# Sheet3.net
KiCad netlist of a schematic drawn in Altium Designer
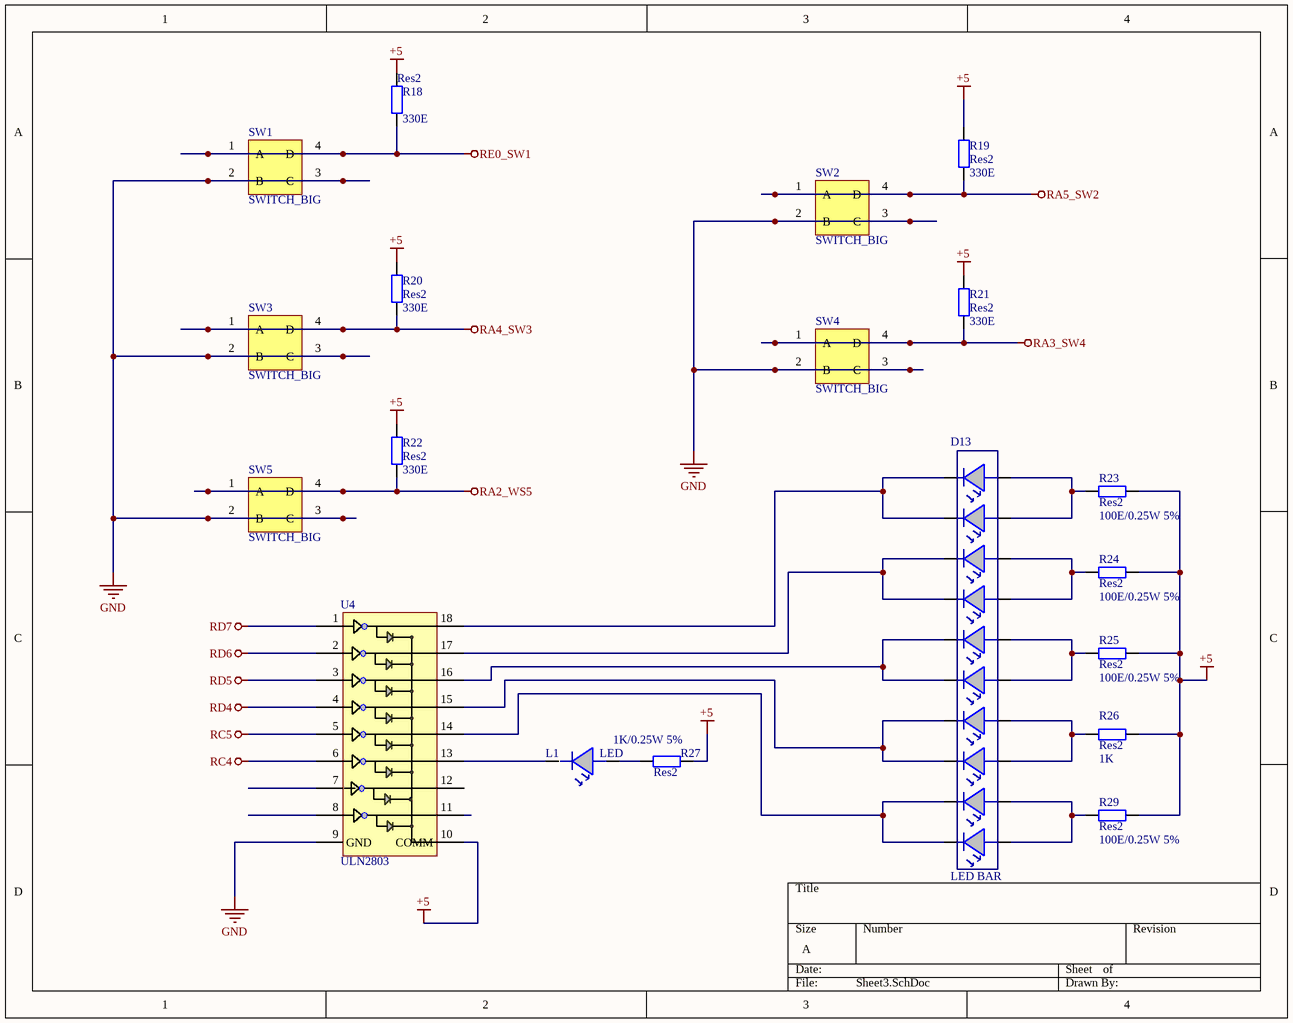
[diagram p0: Sheet3.SchDoc]

(export (version "E")
  (design (tool "Eeschema 10.0.6"))
  (components
    (comp (ref "D13")
      (value "LED BAR")
      (footprint "LED_BAR")
      (libsource (lib "VIJAYIntegrated_Library") (part "LED_BAR"))
    )
    (comp (ref "L1")
      (value "LED")
      (footprint "LED5MM")
      (description "LED_5MM")
      (libsource (lib "Dinesh_New_Integrated_Library") (part "LED_5MM"))
    )
    (comp (ref "R18")
      (value "Res2")
      (footprint "AXIAL-0.4")
      (description "Resistor")
      (fields (field (name "ALTIUM_VALUE") "330E") (field (name "PUBLISHER") "Altium Limited"))
      (libsource (lib "Miscellaneous Devices") (part "Res2"))
    )
    (comp (ref "R19")
      (value "Res2")
      (footprint "AXIAL-0.4")
      (description "Resistor")
      (fields (field (name "ALTIUM_VALUE") "330E") (field (name "PUBLISHER") "Altium Limited"))
      (libsource (lib "Miscellaneous Devices") (part "Res2"))
    )
    (comp (ref "R20")
      (value "Res2")
      (footprint "AXIAL-0.4")
      (description "Resistor")
      (fields (field (name "ALTIUM_VALUE") "330E") (field (name "PUBLISHER") "Altium Limited"))
      (libsource (lib "Miscellaneous Devices") (part "Res2"))
    )
    (comp (ref "R21")
      (value "Res2")
      (footprint "AXIAL-0.4")
      (description "Resistor")
      (fields (field (name "ALTIUM_VALUE") "330E") (field (name "PUBLISHER") "Altium Limited"))
      (libsource (lib "Miscellaneous Devices") (part "Res2"))
    )
    (comp (ref "R22")
      (value "Res2")
      (footprint "AXIAL-0.4")
      (description "Resistor")
      (fields (field (name "ALTIUM_VALUE") "330E") (field (name "PUBLISHER") "Altium Limited"))
      (libsource (lib "Miscellaneous Devices") (part "Res2"))
    )
    (comp (ref "R23")
      (value "Res2")
      (footprint "AXIAL-0.4")
      (description "Resistor")
      (fields (field (name "ALTIUM_VALUE") "100E/0.25W 5%") (field (name "PUBLISHER") "Altium Limited"))
      (libsource (lib "") (part "Res2_1"))
    )
    (comp (ref "R24")
      (value "Res2")
      (footprint "AXIAL-0.4")
      (description "Resistor")
      (fields (field (name "ALTIUM_VALUE") "100E/0.25W 5%") (field (name "PUBLISHER") "Altium Limited"))
      (libsource (lib "") (part "Res2_1"))
    )
    (comp (ref "R25")
      (value "Res2")
      (footprint "AXIAL-0.4")
      (description "Resistor")
      (fields (field (name "ALTIUM_VALUE") "100E/0.25W 5%") (field (name "PUBLISHER") "Altium Limited"))
      (libsource (lib "") (part "Res2_1"))
    )
    (comp (ref "R26")
      (value "Res2")
      (footprint "AXIAL-0.4")
      (description "Resistor")
      (fields (field (name "ALTIUM_VALUE") "1K") (field (name "PUBLISHER") "Altium Limited"))
      (libsource (lib "") (part "Res2_1"))
    )
    (comp (ref "R27")
      (value "Res2")
      (footprint "AXIAL-0.4")
      (description "Resistor")
      (fields (field (name "ALTIUM_VALUE") "1K/0.25W 5%") (field (name "PUBLISHER") "Altium Limited"))
      (libsource (lib "") (part "Res2_2"))
    )
    (comp (ref "R29")
      (value "Res2")
      (footprint "AXIAL-0.4")
      (description "Resistor")
      (fields (field (name "ALTIUM_VALUE") "100E/0.25W 5%") (field (name "PUBLISHER") "Altium Limited"))
      (libsource (lib "") (part "Res2_1"))
    )
    (comp (ref "SW1")
      (value "SWITCH_BIG")
      (footprint "SWITCH - BIG")
      (description "Big size")
      (libsource (lib "Dinesh_New_Integrated_Library") (part "SWITCH_BIG"))
    )
    (comp (ref "SW2")
      (value "SWITCH_BIG")
      (footprint "SWITCH - BIG")
      (description "Big size")
      (libsource (lib "Dinesh_New_Integrated_Library") (part "SWITCH_BIG"))
    )
    (comp (ref "SW3")
      (value "SWITCH_BIG")
      (footprint "SWITCH - BIG")
      (description "Big size")
      (libsource (lib "Dinesh_New_Integrated_Library") (part "SWITCH_BIG"))
    )
    (comp (ref "SW4")
      (value "SWITCH_BIG")
      (footprint "SWITCH - BIG")
      (description "Big size")
      (libsource (lib "Dinesh_New_Integrated_Library") (part "SWITCH_BIG"))
    )
    (comp (ref "SW5")
      (value "SWITCH_BIG")
      (footprint "SWITCH - BIG")
      (description "Big size")
      (libsource (lib "Dinesh_New_Integrated_Library") (part "SWITCH_BIG"))
    )
    (comp (ref "U4")
      (value "ULN2803")
      (footprint "ULN2803")
      (libsource (lib "VIJAYIntegrated_Library") (part "ULN2803"))
    )
  )
  (nets
    (net (code "1") (name "+5") (class "Default")
      (node (ref "R18") (pin "2") (pinfunction "2_2") (pintype "passive"))
      (node (ref "R19") (pin "2") (pinfunction "2_2") (pintype "passive"))
      (node (ref "R20") (pin "2") (pinfunction "2_2") (pintype "passive"))
      (node (ref "R21") (pin "2") (pinfunction "2_2") (pintype "passive"))
      (node (ref "R22") (pin "2") (pinfunction "2_2") (pintype "passive"))
      (node (ref "R23") (pin "2") (pinfunction "2_2") (pintype "passive"))
      (node (ref "R24") (pin "2") (pinfunction "2_2") (pintype "passive"))
      (node (ref "R25") (pin "2") (pinfunction "2_2") (pintype "passive"))
      (node (ref "R26") (pin "2") (pinfunction "2_2") (pintype "passive"))
      (node (ref "R27") (pin "1") (pinfunction "1_1") (pintype "passive"))
      (node (ref "R29") (pin "2") (pinfunction "2_2") (pintype "passive"))
      (node (ref "U4") (pin "10") (pinfunction "COMM_10") (pintype "passive"))
    )
    (net (code "2") (name "GND") (class "Default")
      (node (ref "SW1") (pin "2") (pinfunction "B_2") (pintype "passive"))
      (node (ref "SW1") (pin "3") (pinfunction "C_3") (pintype "passive"))
      (node (ref "SW2") (pin "2") (pinfunction "B_2") (pintype "passive"))
      (node (ref "SW2") (pin "3") (pinfunction "C_3") (pintype "passive"))
      (node (ref "SW3") (pin "2") (pinfunction "B_2") (pintype "passive"))
      (node (ref "SW3") (pin "3") (pinfunction "C_3") (pintype "passive"))
      (node (ref "SW4") (pin "2") (pinfunction "B_2") (pintype "passive"))
      (node (ref "SW4") (pin "3") (pinfunction "C_3") (pintype "passive"))
      (node (ref "SW5") (pin "2") (pinfunction "B_2") (pintype "passive"))
      (node (ref "SW5") (pin "3") (pinfunction "C_3") (pintype "passive"))
      (node (ref "U4") (pin "9") (pinfunction "GND_9") (pintype "passive"))
    )
    (net (code "3") (name "Net-(D13-Pad1)") (class "Default")
      (node (ref "D13") (pin "1") (pinfunction "1_1") (pintype "passive"))
      (node (ref "D13") (pin "2") (pinfunction "2_2") (pintype "passive"))
      (node (ref "R29") (pin "1") (pinfunction "1_1") (pintype "passive"))
    )
    (net (code "4") (name "Net-(D13-Pad3)") (class "Default")
      (node (ref "D13") (pin "3") (pinfunction "3_3") (pintype "passive"))
      (node (ref "D13") (pin "4") (pinfunction "4_4") (pintype "passive"))
      (node (ref "R26") (pin "1") (pinfunction "1_1") (pintype "passive"))
    )
    (net (code "5") (name "Net-(D13-Pad5)") (class "Default")
      (node (ref "D13") (pin "5") (pinfunction "5_5") (pintype "passive"))
      (node (ref "D13") (pin "6") (pinfunction "6_6") (pintype "passive"))
      (node (ref "R25") (pin "1") (pinfunction "1_1") (pintype "passive"))
    )
    (net (code "6") (name "Net-(D13-Pad7)") (class "Default")
      (node (ref "D13") (pin "7") (pinfunction "7_7") (pintype "passive"))
      (node (ref "D13") (pin "8") (pinfunction "8_8") (pintype "passive"))
      (node (ref "R24") (pin "1") (pinfunction "1_1") (pintype "passive"))
    )
    (net (code "7") (name "Net-(D13-Pad10)") (class "Default")
      (node (ref "D13") (pin "10") (pinfunction "10_10") (pintype "passive"))
      (node (ref "D13") (pin "9") (pinfunction "9_9") (pintype "passive"))
      (node (ref "R23") (pin "1") (pinfunction "1_1") (pintype "passive"))
    )
    (net (code "8") (name "Net-(D13-Pad11)") (class "Default")
      (node (ref "D13") (pin "11") (pinfunction "11_11") (pintype "passive"))
      (node (ref "D13") (pin "12") (pinfunction "12_12") (pintype "passive"))
      (node (ref "U4") (pin "18") (pinfunction "18_18") (pintype "passive"))
    )
    (net (code "9") (name "Net-(D13-Pad13)") (class "Default")
      (node (ref "D13") (pin "13") (pinfunction "13_13") (pintype "passive"))
      (node (ref "D13") (pin "14") (pinfunction "14_14") (pintype "passive"))
      (node (ref "U4") (pin "17") (pinfunction "17_17") (pintype "passive"))
    )
    (net (code "10") (name "Net-(D13-Pad15)") (class "Default")
      (node (ref "D13") (pin "15") (pinfunction "15_15") (pintype "passive"))
      (node (ref "D13") (pin "16") (pinfunction "16_16") (pintype "passive"))
      (node (ref "U4") (pin "16") (pinfunction "16_16") (pintype "passive"))
    )
    (net (code "11") (name "Net-(D13-Pad17)") (class "Default")
      (node (ref "D13") (pin "17") (pinfunction "17_17") (pintype "passive"))
      (node (ref "D13") (pin "18") (pinfunction "18_18") (pintype "passive"))
      (node (ref "U4") (pin "15") (pinfunction "15_15") (pintype "passive"))
    )
    (net (code "12") (name "Net-(D13-Pad19)") (class "Default")
      (node (ref "D13") (pin "19") (pinfunction "19_19") (pintype "passive"))
      (node (ref "D13") (pin "20") (pinfunction "20_20") (pintype "passive"))
      (node (ref "U4") (pin "14") (pinfunction "14_14") (pintype "passive"))
    )
    (net (code "13") (name "Net-(L1-A)") (class "Default")
      (node (ref "L1") (pin "1") (pinfunction "A_1") (pintype "passive"))
      (node (ref "R27") (pin "2") (pinfunction "2_2") (pintype "passive"))
    )
    (net (code "14") (name "Net-(L1-B)") (class "Default")
      (node (ref "L1") (pin "2") (pinfunction "B_2") (pintype "passive"))
      (node (ref "U4") (pin "13") (pinfunction "13_13") (pintype "passive"))
    )
    (net (code "15") (name "RA2_WS5") (class "Default")
      (node (ref "R22") (pin "1") (pinfunction "1_1") (pintype "passive"))
      (node (ref "SW5") (pin "1") (pinfunction "A_1") (pintype "passive"))
      (node (ref "SW5") (pin "4") (pinfunction "D_4") (pintype "passive"))
    )
    (net (code "16") (name "RA3_SW4") (class "Default")
      (node (ref "R21") (pin "1") (pinfunction "1_1") (pintype "passive"))
      (node (ref "SW4") (pin "1") (pinfunction "A_1") (pintype "passive"))
      (node (ref "SW4") (pin "4") (pinfunction "D_4") (pintype "passive"))
    )
    (net (code "17") (name "RA4_SW3") (class "Default")
      (node (ref "R20") (pin "1") (pinfunction "1_1") (pintype "passive"))
      (node (ref "SW3") (pin "1") (pinfunction "A_1") (pintype "passive"))
      (node (ref "SW3") (pin "4") (pinfunction "D_4") (pintype "passive"))
    )
    (net (code "18") (name "RA5_SW2") (class "Default")
      (node (ref "R19") (pin "1") (pinfunction "1_1") (pintype "passive"))
      (node (ref "SW2") (pin "1") (pinfunction "A_1") (pintype "passive"))
      (node (ref "SW2") (pin "4") (pinfunction "D_4") (pintype "passive"))
    )
    (net (code "19") (name "RC4") (class "Default")
      (node (ref "U4") (pin "6") (pinfunction "6_6") (pintype "passive"))
    )
    (net (code "20") (name "RC5") (class "Default")
      (node (ref "U4") (pin "5") (pinfunction "5_5") (pintype "passive"))
    )
    (net (code "21") (name "RD4") (class "Default")
      (node (ref "U4") (pin "4") (pinfunction "4_4") (pintype "passive"))
    )
    (net (code "22") (name "RD5") (class "Default")
      (node (ref "U4") (pin "3") (pinfunction "3_3") (pintype "passive"))
    )
    (net (code "23") (name "RD6") (class "Default")
      (node (ref "U4") (pin "2") (pinfunction "2_2") (pintype "passive"))
    )
    (net (code "24") (name "RD7") (class "Default")
      (node (ref "U4") (pin "1") (pinfunction "1_1") (pintype "passive"))
    )
    (net (code "25") (name "RE0_SW1") (class "Default")
      (node (ref "R18") (pin "1") (pinfunction "1_1") (pintype "passive"))
      (node (ref "SW1") (pin "1") (pinfunction "A_1") (pintype "passive"))
      (node (ref "SW1") (pin "4") (pinfunction "D_4") (pintype "passive"))
    )
    (net (code "26") (name "unconnected-(U4-Pad7)") (class "Default")
      (node (ref "U4") (pin "7") (pinfunction "7_7") (pintype "passive"))
    )
    (net (code "27") (name "unconnected-(U4-Pad8)") (class "Default")
      (node (ref "U4") (pin "8") (pinfunction "8_8") (pintype "passive"))
    )
    (net (code "28") (name "unconnected-(U4-Pad11)") (class "Default")
      (node (ref "U4") (pin "11") (pinfunction "11_11") (pintype "passive"))
    )
    (net (code "29") (name "unconnected-(U4-Pad12)") (class "Default")
      (node (ref "U4") (pin "12") (pinfunction "12_12") (pintype "passive"))
    )
  )
)
